# captivate_proximity.net
KiCad netlist of a schematic drawn in Altium Designer
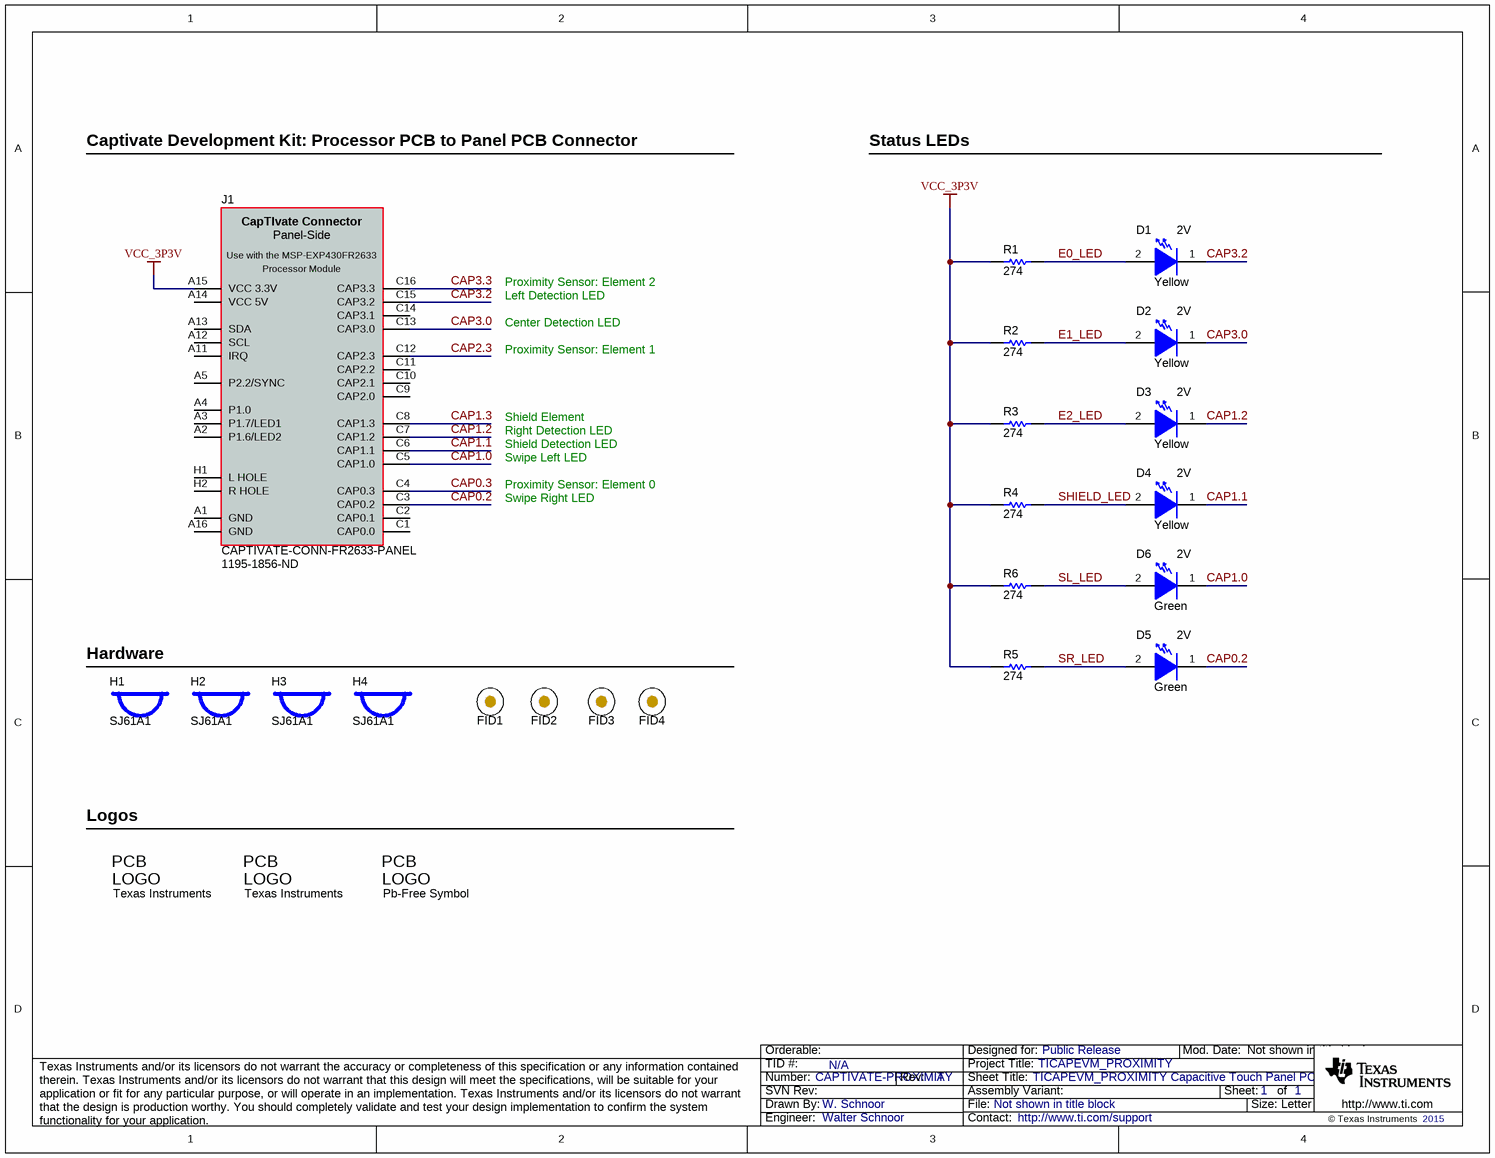
[diagram p0: captivate_proximity.SchDoc]

(export (version "E")
  (design (tool "Eeschema 10.0.6"))
  (components
    (comp (ref "D1")
      (value "Yellow")
      (footprint "WL-SMCW_YELLOW")
      (description "LED, Yellow, SMD")
      (fields
        (field (name "MANUFACTURER") "Wurth Elektronik eiSos")
        (field (name "PARTNUMBER") "150060YS75000")
        (field (name "VALUE2") "2V")
        (field (name "PUBLISHER") "Texas Instruments")
      )
      (libsource (lib "LED") (part "150060YS75000"))
    )
    (comp (ref "D2")
      (value "Yellow")
      (footprint "WL-SMCW_YELLOW")
      (description "LED, Yellow, SMD")
      (fields
        (field (name "MANUFACTURER") "Wurth Elektronik eiSos")
        (field (name "PARTNUMBER") "150060YS75000")
        (field (name "VALUE2") "2V")
        (field (name "PUBLISHER") "Texas Instruments")
      )
      (libsource (lib "LED") (part "150060YS75000"))
    )
    (comp (ref "D3")
      (value "Yellow")
      (footprint "WL-SMCW_YELLOW")
      (description "LED, Yellow, SMD")
      (fields
        (field (name "MANUFACTURER") "Wurth Elektronik eiSos")
        (field (name "PARTNUMBER") "150060YS75000")
        (field (name "VALUE2") "2V")
        (field (name "PUBLISHER") "Texas Instruments")
      )
      (libsource (lib "LED") (part "150060YS75000"))
    )
    (comp (ref "D4")
      (value "Yellow")
      (footprint "WL-SMCW_YELLOW")
      (description "LED, Yellow, SMD")
      (fields
        (field (name "MANUFACTURER") "Wurth Elektronik eiSos")
        (field (name "PARTNUMBER") "150060YS75000")
        (field (name "VALUE2") "2V")
        (field (name "PUBLISHER") "Texas Instruments")
      )
      (libsource (lib "LED") (part "150060YS75000"))
    )
    (comp (ref "D5")
      (value "Green")
      (footprint "WL-SMCW_GREEN")
      (description "LED, Green, SMD")
      (fields
        (field (name "MANUFACTURER") "Wurth Elektronik eiSos")
        (field (name "PARTNUMBER") "150060VS75000")
        (field (name "VALUE2") "2V")
        (field (name "PUBLISHER") "Texas Instruments")
      )
      (libsource (lib "LED") (part "150060VS75000"))
    )
    (comp (ref "D6")
      (value "Green")
      (footprint "WL-SMCW_GREEN")
      (description "LED, Green, SMD")
      (fields
        (field (name "MANUFACTURER") "Wurth Elektronik eiSos")
        (field (name "PARTNUMBER") "150060VS75000")
        (field (name "VALUE2") "2V")
        (field (name "PUBLISHER") "Texas Instruments")
      )
      (libsource (lib "LED") (part "150060VS75000"))
    )
    (comp (ref "FID1")
      (value "Fiducial")
      (footprint "Fiducial10-20")
      (description "Fiducial mark.  There is nothing to buy or mount.")
      (fields (field (name "SYMBOLCREATOR") "codlsc") (field (name "PUBLISHER") "Texas Instruments"))
      (libsource (lib "MiscParts") (part "Fiducial"))
    )
    (comp (ref "FID2")
      (value "Fiducial")
      (footprint "Fiducial10-20")
      (description "Fiducial mark.  There is nothing to buy or mount.")
      (fields (field (name "SYMBOLCREATOR") "codlsc") (field (name "PUBLISHER") "Texas Instruments"))
      (libsource (lib "MiscParts") (part "Fiducial"))
    )
    (comp (ref "FID3")
      (value "Fiducial")
      (footprint "Fiducial10-20")
      (description "Fiducial mark.  There is nothing to buy or mount.")
      (fields (field (name "SYMBOLCREATOR") "codlsc") (field (name "PUBLISHER") "Texas Instruments"))
      (libsource (lib "MiscParts") (part "Fiducial"))
    )
    (comp (ref "FID4")
      (value "Fiducial")
      (footprint "Fiducial10-20")
      (description "Fiducial mark.  There is nothing to buy or mount.")
      (fields (field (name "SYMBOLCREATOR") "codlsc") (field (name "PUBLISHER") "Texas Instruments"))
      (libsource (lib "MiscParts") (part "Fiducial"))
    )
    (comp (ref "H1")
      (value "SJ61A1")
      (footprint "Bumpon_SJ61A1")
      (description "Bumpon, Cylindrical, 0.312 X 0.200, Black")
      (fields
        (field (name "MANUFACTURER") "3M")
        (field (name "SYMBOLCREATOR") "a0412235")
        (field (name "PUBLISHER") "Texas Instruments")
      )
      (libsource (lib "Hardware") (part "SJ61A1"))
    )
    (comp (ref "H2")
      (value "SJ61A1")
      (footprint "Bumpon_SJ61A1")
      (description "Bumpon, Cylindrical, 0.312 X 0.200, Black")
      (fields
        (field (name "MANUFACTURER") "3M")
        (field (name "SYMBOLCREATOR") "a0412235")
        (field (name "PUBLISHER") "Texas Instruments")
      )
      (libsource (lib "Hardware") (part "SJ61A1"))
    )
    (comp (ref "H3")
      (value "SJ61A1")
      (footprint "Bumpon_SJ61A1")
      (description "Bumpon, Cylindrical, 0.312 X 0.200, Black")
      (fields
        (field (name "MANUFACTURER") "3M")
        (field (name "SYMBOLCREATOR") "a0412235")
        (field (name "PUBLISHER") "Texas Instruments")
      )
      (libsource (lib "Hardware") (part "SJ61A1"))
    )
    (comp (ref "H4")
      (value "SJ61A1")
      (footprint "Bumpon_SJ61A1")
      (description "Bumpon, Cylindrical, 0.312 X 0.200, Black")
      (fields
        (field (name "MANUFACTURER") "3M")
        (field (name "SYMBOLCREATOR") "a0412235")
        (field (name "PUBLISHER") "Texas Instruments")
      )
      (libsource (lib "Hardware") (part "SJ61A1"))
    )
    (comp (ref "J1")
      (value "CAPTIVATE-CONN-FR2633-PANEL")
      (footprint "CAPTIVATE-CONN-48")
      (description "CapTIvate Panel-Side Connector, 3x16, 100mil, TH, RA, M, MSP-EXP430FR2633")
      (fields
        (field (name "MANUFACTURER") "Used in BOM report")
        (field (name "SUPPLIER PART NUMBER 1") "1195-1856-ND")
        (field (name "SYMBOLCREATOR") "a0273983")
      )
      (libsource (lib "CapTIvate_Connector") (part "CAPTIVATE-CONN-MSP-EXP430FR2633-PANEL"))
    )
    (comp (ref "LeadFreeLogo")
      (value "Pb-Free Symbol")
      (footprint "Pb-Free_Overlay_Medium")
      (fields (field (name "SYMBOLCREATOR") "a0412235") (field (name "PUBLISHER") "Texas Instruments"))
      (libsource (lib "Logos") (part "Pb-Free"))
    )
    (comp (ref "R1")
      (value "CRCW0603274RFKEA")
      (footprint "0603")
      (description "RES, 274, 1%, 0.1 W, 0603")
      (fields
        (field (name "VALUEDISPLAYED") "274")
        (field (name "MANUFACTURER") "Vishay-Dale")
        (field (name "PUBLISHER") "Texas Instruments")
      )
      (libsource (lib "Resistor_0603") (part "CRCW0603274RFKEA"))
    )
    (comp (ref "R2")
      (value "CRCW0603274RFKEA")
      (footprint "0603")
      (description "RES, 274, 1%, 0.1 W, 0603")
      (fields
        (field (name "VALUEDISPLAYED") "274")
        (field (name "MANUFACTURER") "Vishay-Dale")
        (field (name "PUBLISHER") "Texas Instruments")
      )
      (libsource (lib "Resistor_0603") (part "CRCW0603274RFKEA"))
    )
    (comp (ref "R3")
      (value "CRCW0603274RFKEA")
      (footprint "0603")
      (description "RES, 274, 1%, 0.1 W, 0603")
      (fields
        (field (name "VALUEDISPLAYED") "274")
        (field (name "MANUFACTURER") "Vishay-Dale")
        (field (name "PUBLISHER") "Texas Instruments")
      )
      (libsource (lib "Resistor_0603") (part "CRCW0603274RFKEA"))
    )
    (comp (ref "R4")
      (value "CRCW0603274RFKEA")
      (footprint "0603")
      (description "RES, 274, 1%, 0.1 W, 0603")
      (fields
        (field (name "VALUEDISPLAYED") "274")
        (field (name "MANUFACTURER") "Vishay-Dale")
        (field (name "PUBLISHER") "Texas Instruments")
      )
      (libsource (lib "Resistor_0603") (part "CRCW0603274RFKEA"))
    )
    (comp (ref "R5")
      (value "CRCW0603274RFKEA")
      (footprint "0603")
      (description "RES, 274, 1%, 0.1 W, 0603")
      (fields
        (field (name "VALUEDISPLAYED") "274")
        (field (name "MANUFACTURER") "Vishay-Dale")
        (field (name "PUBLISHER") "Texas Instruments")
      )
      (libsource (lib "Resistor_0603") (part "CRCW0603274RFKEA"))
    )
    (comp (ref "R6")
      (value "CRCW0603274RFKEA")
      (footprint "0603")
      (description "RES, 274, 1%, 0.1 W, 0603")
      (fields
        (field (name "VALUEDISPLAYED") "274")
        (field (name "MANUFACTURER") "Vishay-Dale")
        (field (name "PUBLISHER") "Texas Instruments")
      )
      (libsource (lib "Resistor_0603") (part "CRCW0603274RFKEA"))
    )
    (comp (ref "TI Logo")
      (value "Texas Instruments")
      (footprint "TI_Horizontal_Overlay_Small")
      (description "Texas Instrument Corporate Signature")
      (fields (field (name "SYMBOLCREATOR") "a0412235") (field (name "PUBLISHER") "Texas Instruments"))
      (libsource (lib "Logos") (part "TI_Logo"))
    )
    (comp (ref "TILogo_Back")
      (value "Texas Instruments")
      (footprint "TI_Horizontal_Overlay_Medium")
      (description "Texas Instrument Corporate Signature")
      (fields (field (name "SYMBOLCREATOR") "a0412235") (field (name "PUBLISHER") "Texas Instruments"))
      (libsource (lib "Logos") (part "TI_Logo"))
    )
  )
  (nets
    (net (code "1") (name "/CAP0.2") (class "Default")
      (node (ref "D5") (pin "1") (pinfunction "K_1") (pintype "passive"))
      (node (ref "J1") (pin "C3") (pinfunction "CAP0.2_C3") (pintype "passive"))
    )
    (net (code "2") (name "/CAP0.3") (class "Default")
      (node (ref "J1") (pin "C4") (pinfunction "CAP0.3_C4") (pintype "passive"))
    )
    (net (code "3") (name "/CAP1.0") (class "Default")
      (node (ref "D6") (pin "1") (pinfunction "K_1") (pintype "passive"))
      (node (ref "J1") (pin "C5") (pinfunction "CAP1.0_C5") (pintype "passive"))
    )
    (net (code "4") (name "/CAP1.1") (class "Default")
      (node (ref "D4") (pin "1") (pinfunction "K_1") (pintype "passive"))
      (node (ref "J1") (pin "C6") (pinfunction "CAP1.1_C6") (pintype "passive"))
    )
    (net (code "5") (name "/CAP1.2") (class "Default")
      (node (ref "D3") (pin "1") (pinfunction "K_1") (pintype "passive"))
      (node (ref "J1") (pin "C7") (pinfunction "CAP1.2_C7") (pintype "passive"))
    )
    (net (code "6") (name "/CAP1.3") (class "Default")
      (node (ref "J1") (pin "C8") (pinfunction "CAP1.3_C8") (pintype "passive"))
    )
    (net (code "7") (name "/CAP2.3") (class "Default")
      (node (ref "J1") (pin "C12") (pinfunction "CAP2.3_C12") (pintype "passive"))
    )
    (net (code "8") (name "/CAP3.0") (class "Default")
      (node (ref "D2") (pin "1") (pinfunction "K_1") (pintype "passive"))
      (node (ref "J1") (pin "C13") (pinfunction "CAP3.0_C13") (pintype "passive"))
    )
    (net (code "9") (name "/CAP3.2") (class "Default")
      (node (ref "D1") (pin "1") (pinfunction "K_1") (pintype "passive"))
      (node (ref "J1") (pin "C15") (pinfunction "CAP3.2_C15") (pintype "passive"))
    )
    (net (code "10") (name "/CAP3.3") (class "Default")
      (node (ref "J1") (pin "C16") (pinfunction "CAP3.3_C16") (pintype "passive"))
    )
    (net (code "11") (name "/E0_LED") (class "Default")
      (node (ref "D1") (pin "2") (pinfunction "A_2") (pintype "passive"))
      (node (ref "R1") (pin "2") (pinfunction "2_2") (pintype "passive"))
    )
    (net (code "12") (name "/E1_LED") (class "Default")
      (node (ref "D2") (pin "2") (pinfunction "A_2") (pintype "passive"))
      (node (ref "R2") (pin "2") (pinfunction "2_2") (pintype "passive"))
    )
    (net (code "13") (name "/E2_LED") (class "Default")
      (node (ref "D3") (pin "2") (pinfunction "A_2") (pintype "passive"))
      (node (ref "R3") (pin "2") (pinfunction "2_2") (pintype "passive"))
    )
    (net (code "14") (name "/SHIELD_LED") (class "Default")
      (node (ref "D4") (pin "2") (pinfunction "A_2") (pintype "passive"))
      (node (ref "R4") (pin "2") (pinfunction "2_2") (pintype "passive"))
    )
    (net (code "15") (name "/SL_LED") (class "Default")
      (node (ref "D6") (pin "2") (pinfunction "A_2") (pintype "passive"))
      (node (ref "R6") (pin "2") (pinfunction "2_2") (pintype "passive"))
    )
    (net (code "16") (name "/SR_LED") (class "Default")
      (node (ref "D5") (pin "2") (pinfunction "A_2") (pintype "passive"))
      (node (ref "R5") (pin "2") (pinfunction "2_2") (pintype "passive"))
    )
    (net (code "17") (name "VCC_3P3V") (class "Default")
      (node (ref "J1") (pin "A15") (pinfunction "VCC_3.3V_A15") (pintype "power_in"))
      (node (ref "R1") (pin "1") (pinfunction "1_1") (pintype "passive"))
      (node (ref "R2") (pin "1") (pinfunction "1_1") (pintype "passive"))
      (node (ref "R3") (pin "1") (pinfunction "1_1") (pintype "passive"))
      (node (ref "R4") (pin "1") (pinfunction "1_1") (pintype "passive"))
      (node (ref "R5") (pin "1") (pinfunction "1_1") (pintype "passive"))
      (node (ref "R6") (pin "1") (pinfunction "1_1") (pintype "passive"))
    )
    (net (code "18") (name "unconnected-(J1-CAP0.0-PadC1)") (class "Default")
      (node (ref "J1") (pin "C1") (pinfunction "CAP0.0_C1") (pintype "passive"))
    )
    (net (code "19") (name "unconnected-(J1-CAP0.1-PadC2)") (class "Default")
      (node (ref "J1") (pin "C2") (pinfunction "CAP0.1_C2") (pintype "passive"))
    )
    (net (code "20") (name "unconnected-(J1-CAP2.0-PadC9)") (class "Default")
      (node (ref "J1") (pin "C9") (pinfunction "CAP2.0_C9") (pintype "passive"))
    )
    (net (code "21") (name "unconnected-(J1-CAP2.1-PadC10)") (class "Default")
      (node (ref "J1") (pin "C10") (pinfunction "CAP2.1_C10") (pintype "passive"))
    )
    (net (code "22") (name "unconnected-(J1-CAP2.2-PadC11)") (class "Default")
      (node (ref "J1") (pin "C11") (pinfunction "CAP2.2_C11") (pintype "passive"))
    )
    (net (code "23") (name "unconnected-(J1-CAP3.1-PadC14)") (class "Default")
      (node (ref "J1") (pin "C14") (pinfunction "CAP3.1_C14") (pintype "passive"))
    )
    (net (code "24") (name "unconnected-(J1-GND-PadA1)") (class "Default")
      (node (ref "J1") (pin "A1") (pinfunction "GND_A1") (pintype "power_in"))
    )
    (net (code "25") (name "unconnected-(J1-GND-PadA16)") (class "Default")
      (node (ref "J1") (pin "A16") (pinfunction "GND_A16") (pintype "power_in"))
    )
    (net (code "26") (name "unconnected-(J1-IRQ-PadA11)") (class "Default")
      (node (ref "J1") (pin "A11") (pinfunction "IRQ_A11") (pintype "open_collector"))
    )
    (net (code "27") (name "unconnected-(J1-L_HOLE-PadH1)") (class "Default")
      (node (ref "J1") (pin "H1") (pinfunction "L_HOLE_H1") (pintype "passive"))
    )
    (net (code "28") (name "unconnected-(J1-P1.0-PadA4)") (class "Default")
      (node (ref "J1") (pin "A4") (pinfunction "P1.0_A4") (pintype "open_collector"))
    )
    (net (code "29") (name "unconnected-(J1-P1.6{slash}LED2-PadA2)") (class "Default")
      (node (ref "J1") (pin "A2") (pinfunction "P1.6/LED2_A2") (pintype "open_collector"))
    )
    (net (code "30") (name "unconnected-(J1-P1.7{slash}LED1-PadA3)") (class "Default")
      (node (ref "J1") (pin "A3") (pinfunction "P1.7/LED1_A3") (pintype "open_collector"))
    )
    (net (code "31") (name "unconnected-(J1-P2.2{slash}SYNC-PadA5)") (class "Default")
      (node (ref "J1") (pin "A5") (pinfunction "P2.2/SYNC_A5") (pintype "open_collector"))
    )
    (net (code "32") (name "unconnected-(J1-R_HOLE-PadH2)") (class "Default")
      (node (ref "J1") (pin "H2") (pinfunction "R_HOLE_H2") (pintype "passive"))
    )
    (net (code "33") (name "unconnected-(J1-SCL-PadA12)") (class "Default")
      (node (ref "J1") (pin "A12") (pinfunction "SCL_A12") (pintype "open_collector"))
    )
    (net (code "34") (name "unconnected-(J1-SDA-PadA13)") (class "Default")
      (node (ref "J1") (pin "A13") (pinfunction "SDA_A13") (pintype "open_collector"))
    )
    (net (code "35") (name "unconnected-(J1-VCC_5V-PadA14)") (class "Default")
      (node (ref "J1") (pin "A14") (pinfunction "VCC_5V_A14") (pintype "power_in"))
    )
  )
)
